# Freedom_Board_Interface.net
KiCad netlist of a schematic drawn in Altium Designer
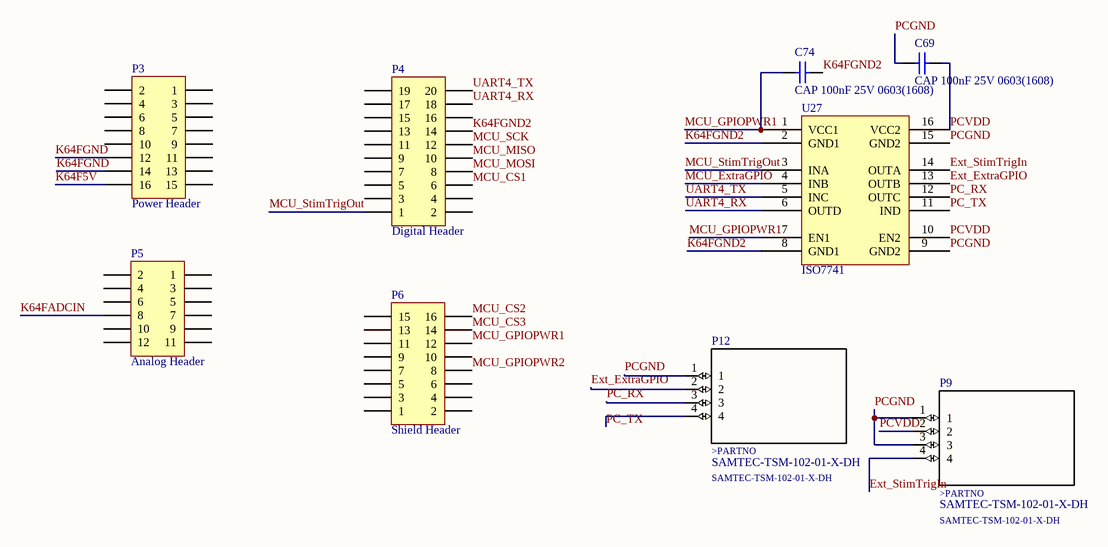
[diagram p0: Freedom Board Interface.SchDoc]

(export (version "E")
  (design (tool "Eeschema 10.0.6"))
  (components
    (comp (ref "C69")
      (value "CAP 100nF 25V 0603(1608)")
      (footprint "CAPC0603(1608)100_N")
      (description "CAP 100nF 25V ±20% 0603 (1608 Metric) Thickness 1mm SMD")
      (fields (field (name "TOLERANCE") "Â±20%"))
      (libsource (lib "Altium Content Vault") (part "CAP"))
    )
    (comp (ref "C74")
      (value "CAP 100nF 25V 0603(1608)")
      (footprint "CAPC0603(1608)100_N")
      (description "CAP 100nF 25V ±20% 0603 (1608 Metric) Thickness 1mm SMD")
      (fields (field (name "TOLERANCE") "Â±20%"))
      (libsource (lib "Altium Content Vault") (part "CAP"))
    )
    (comp (ref "P3")
      (value "Power Header")
      (footprint "HDR2X8")
      (description "Header, 8-Pin, Dual row")
      (fields (field (name "PUBLISHER") "Altium Limited"))
      (libsource (lib "") (part "Header 8X2_1"))
    )
    (comp (ref "P4")
      (value "Digital Header")
      (footprint "HDR2X10")
      (description "Header, 10-Pin, Dual row")
      (fields (field (name "PUBLISHER") "Altium Limited"))
      (libsource (lib "Miscellaneous Connectors") (part "Header 10X2"))
    )
    (comp (ref "P5")
      (value "Analog Header")
      (footprint "HDR2X6")
      (description "Header, 6-Pin, Dual row")
      (fields (field (name "PUBLISHER") "Altium Limited"))
      (libsource (lib "Miscellaneous Connectors") (part "Header 6X2"))
    )
    (comp (ref "P6")
      (value "Shield Header")
      (footprint "HDR2X8")
      (description "Header, 8-Pin, Dual row")
      (fields (field (name "PUBLISHER") "Altium Limited"))
      (libsource (lib "Miscellaneous Connectors") (part "Header 8X2"))
    )
    (comp (ref "P9")
      (value "SAMTEC-TSM-102-01-X-DH")
      (footprint "*SAMTEC-TSM-102-01-X-DH")
      (description "Conn Unshrouded Header HDR 4 POS 2.54mm Solder RA SMD")
      (fields (field (name "MF") "Samtec Inc.") (field (name "DIGI-KEY_PART_NUMBER") "TSM-102-01-F-DH-ND"))
      (libsource (lib "SAMTEC-TSM-102-01-X-DH") (part "SAMTEC-TSM-102-01-X-DH"))
    )
    (comp (ref "P12")
      (value "SAMTEC-TSM-102-01-X-DH")
      (footprint "*SAMTEC-TSM-102-01-X-DH")
      (description "Conn Unshrouded Header HDR 4 POS 2.54mm Solder RA SMD")
      (fields (field (name "MF") "Samtec Inc.") (field (name "DIGI-KEY_PART_NUMBER") "TSM-102-01-F-DH-ND"))
      (libsource (lib "SAMTEC-TSM-102-01-X-DH") (part "SAMTEC-TSM-102-01-X-DH"))
    )
    (comp (ref "U27")
      (value "ISO7741")
      (footprint "16SSOP JEDEC MO-137 AB")
      (libsource (lib "ar5113_Altium_Library") (part "ISO7741"))
    )
  )
  (nets
    (net (code "1") (name "/Ext_ExtraGPIO") (class "Default")
      (node (ref "P12") (pin "2") (pinfunction "2_2") (pintype "bidirectional"))
      (node (ref "U27") (pin "13") (pinfunction "OUTB_13") (pintype "passive"))
    )
    (net (code "2") (name "/Ext_StimTrigIn") (class "Default")
      (node (ref "P9") (pin "4") (pinfunction "4_4") (pintype "bidirectional"))
      (node (ref "U27") (pin "14") (pinfunction "OUTA_14") (pintype "passive"))
    )
    (net (code "3") (name "/K64F5V") (class "Default")
      (node (ref "P3") (pin "16") (pinfunction "16_16") (pintype "passive"))
    )
    (net (code "4") (name "/K64FADCIN") (class "Default")
      (node (ref "P5") (pin "8") (pinfunction "8_8") (pintype "passive"))
    )
    (net (code "5") (name "/K64FGND") (class "Default")
      (node (ref "P3") (pin "12") (pinfunction "12_12") (pintype "passive"))
      (node (ref "P3") (pin "14") (pinfunction "14_14") (pintype "passive"))
    )
    (net (code "6") (name "/K64FGND2") (class "Default")
      (node (ref "C74") (pin "1") (pinfunction "1_1") (pintype "passive"))
      (node (ref "P4") (pin "14") (pinfunction "14_14") (pintype "passive"))
      (node (ref "U27") (pin "2") (pinfunction "GND1_2") (pintype "passive"))
      (node (ref "U27") (pin "8") (pinfunction "GND1_8") (pintype "passive"))
    )
    (net (code "7") (name "/MCU_CS1") (class "Default")
      (node (ref "P4") (pin "6") (pinfunction "6_6") (pintype "passive"))
    )
    (net (code "8") (name "/MCU_CS2") (class "Default")
      (node (ref "P6") (pin "16") (pinfunction "16_16") (pintype "passive"))
    )
    (net (code "9") (name "/MCU_CS3") (class "Default")
      (node (ref "P6") (pin "14") (pinfunction "14_14") (pintype "passive"))
    )
    (net (code "10") (name "/MCU_ExtraGPIO") (class "Default")
      (node (ref "U27") (pin "4") (pinfunction "INB_4") (pintype "passive"))
    )
    (net (code "11") (name "/MCU_GPIOPWR1") (class "Default")
      (node (ref "C74") (pin "2") (pinfunction "2_2") (pintype "passive"))
      (node (ref "P6") (pin "12") (pinfunction "12_12") (pintype "passive"))
      (node (ref "U27") (pin "1") (pinfunction "VCC1_1") (pintype "passive"))
      (node (ref "U27") (pin "7") (pinfunction "EN1_7") (pintype "passive"))
    )
    (net (code "12") (name "/MCU_GPIOPWR2") (class "Default")
      (node (ref "P6") (pin "8") (pinfunction "8_8") (pintype "passive"))
    )
    (net (code "13") (name "/MCU_MISO") (class "Default")
      (node (ref "P4") (pin "10") (pinfunction "10_10") (pintype "passive"))
    )
    (net (code "14") (name "/MCU_MOSI") (class "Default")
      (node (ref "P4") (pin "8") (pinfunction "8_8") (pintype "passive"))
    )
    (net (code "15") (name "/MCU_SCK") (class "Default")
      (node (ref "P4") (pin "12") (pinfunction "12_12") (pintype "passive"))
    )
    (net (code "16") (name "/MCU_StimTrigOut") (class "Default")
      (node (ref "P4") (pin "1") (pinfunction "1_1") (pintype "passive"))
      (node (ref "U27") (pin "3") (pinfunction "INA_3") (pintype "passive"))
    )
    (net (code "17") (name "/PCGND") (class "Default")
      (node (ref "C69") (pin "2") (pinfunction "2_2") (pintype "passive"))
      (node (ref "P12") (pin "1") (pinfunction "1_1") (pintype "bidirectional"))
      (node (ref "P9") (pin "1") (pinfunction "1_1") (pintype "bidirectional"))
      (node (ref "P9") (pin "3") (pinfunction "3_3") (pintype "bidirectional"))
      (node (ref "U27") (pin "15") (pinfunction "GND2_15") (pintype "passive"))
      (node (ref "U27") (pin "9") (pinfunction "GND2_9") (pintype "passive"))
    )
    (net (code "18") (name "/PCVDD") (class "Default")
      (node (ref "C69") (pin "1") (pinfunction "1_1") (pintype "passive"))
      (node (ref "P9") (pin "2") (pinfunction "2_2") (pintype "bidirectional"))
      (node (ref "U27") (pin "10") (pinfunction "EN2_10") (pintype "passive"))
      (node (ref "U27") (pin "16") (pinfunction "VCC2_16") (pintype "passive"))
    )
    (net (code "19") (name "/PC_RX") (class "Default")
      (node (ref "P12") (pin "3") (pinfunction "3_3") (pintype "bidirectional"))
      (node (ref "U27") (pin "12") (pinfunction "OUTC_12") (pintype "passive"))
    )
    (net (code "20") (name "/PC_TX") (class "Default")
      (node (ref "P12") (pin "4") (pinfunction "4_4") (pintype "bidirectional"))
      (node (ref "U27") (pin "11") (pinfunction "IND_11") (pintype "passive"))
    )
    (net (code "21") (name "/UART4_RX") (class "Default")
      (node (ref "P4") (pin "18") (pinfunction "18_18") (pintype "passive"))
      (node (ref "U27") (pin "6") (pinfunction "OUTD_6") (pintype "passive"))
    )
    (net (code "22") (name "/UART4_TX") (class "Default")
      (node (ref "P4") (pin "20") (pinfunction "20_20") (pintype "passive"))
      (node (ref "U27") (pin "5") (pinfunction "INC_5") (pintype "passive"))
    )
    (net (code "23") (name "unconnected-(P3-Pad1)") (class "Default")
      (node (ref "P3") (pin "1") (pinfunction "1_1") (pintype "passive"))
    )
    (net (code "24") (name "unconnected-(P3-Pad2)") (class "Default")
      (node (ref "P3") (pin "2") (pinfunction "2_2") (pintype "passive"))
    )
    (net (code "25") (name "unconnected-(P3-Pad3)") (class "Default")
      (node (ref "P3") (pin "3") (pinfunction "3_3") (pintype "passive"))
    )
    (net (code "26") (name "unconnected-(P3-Pad4)") (class "Default")
      (node (ref "P3") (pin "4") (pinfunction "4_4") (pintype "passive"))
    )
    (net (code "27") (name "unconnected-(P3-Pad5)") (class "Default")
      (node (ref "P3") (pin "5") (pinfunction "5_5") (pintype "passive"))
    )
    (net (code "28") (name "unconnected-(P3-Pad6)") (class "Default")
      (node (ref "P3") (pin "6") (pinfunction "6_6") (pintype "passive"))
    )
    (net (code "29") (name "unconnected-(P3-Pad7)") (class "Default")
      (node (ref "P3") (pin "7") (pinfunction "7_7") (pintype "passive"))
    )
    (net (code "30") (name "unconnected-(P3-Pad8)") (class "Default")
      (node (ref "P3") (pin "8") (pinfunction "8_8") (pintype "passive"))
    )
    (net (code "31") (name "unconnected-(P3-Pad9)") (class "Default")
      (node (ref "P3") (pin "9") (pinfunction "9_9") (pintype "passive"))
    )
    (net (code "32") (name "unconnected-(P3-Pad10)") (class "Default")
      (node (ref "P3") (pin "10") (pinfunction "10_10") (pintype "passive"))
    )
    (net (code "33") (name "unconnected-(P3-Pad11)") (class "Default")
      (node (ref "P3") (pin "11") (pinfunction "11_11") (pintype "passive"))
    )
    (net (code "34") (name "unconnected-(P3-Pad13)") (class "Default")
      (node (ref "P3") (pin "13") (pinfunction "13_13") (pintype "passive"))
    )
    (net (code "35") (name "unconnected-(P3-Pad15)") (class "Default")
      (node (ref "P3") (pin "15") (pinfunction "15_15") (pintype "passive"))
    )
    (net (code "36") (name "unconnected-(P4-Pad2)") (class "Default")
      (node (ref "P4") (pin "2") (pinfunction "2_2") (pintype "passive"))
    )
    (net (code "37") (name "unconnected-(P4-Pad3)") (class "Default")
      (node (ref "P4") (pin "3") (pinfunction "3_3") (pintype "passive"))
    )
    (net (code "38") (name "unconnected-(P4-Pad4)") (class "Default")
      (node (ref "P4") (pin "4") (pinfunction "4_4") (pintype "passive"))
    )
    (net (code "39") (name "unconnected-(P4-Pad5)") (class "Default")
      (node (ref "P4") (pin "5") (pinfunction "5_5") (pintype "passive"))
    )
    (net (code "40") (name "unconnected-(P4-Pad7)") (class "Default")
      (node (ref "P4") (pin "7") (pinfunction "7_7") (pintype "passive"))
    )
    (net (code "41") (name "unconnected-(P4-Pad9)") (class "Default")
      (node (ref "P4") (pin "9") (pinfunction "9_9") (pintype "passive"))
    )
    (net (code "42") (name "unconnected-(P4-Pad11)") (class "Default")
      (node (ref "P4") (pin "11") (pinfunction "11_11") (pintype "passive"))
    )
    (net (code "43") (name "unconnected-(P4-Pad13)") (class "Default")
      (node (ref "P4") (pin "13") (pinfunction "13_13") (pintype "passive"))
    )
    (net (code "44") (name "unconnected-(P4-Pad15)") (class "Default")
      (node (ref "P4") (pin "15") (pinfunction "15_15") (pintype "passive"))
    )
    (net (code "45") (name "unconnected-(P4-Pad16)") (class "Default")
      (node (ref "P4") (pin "16") (pinfunction "16_16") (pintype "passive"))
    )
    (net (code "46") (name "unconnected-(P4-Pad17)") (class "Default")
      (node (ref "P4") (pin "17") (pinfunction "17_17") (pintype "passive"))
    )
    (net (code "47") (name "unconnected-(P4-Pad19)") (class "Default")
      (node (ref "P4") (pin "19") (pinfunction "19_19") (pintype "passive"))
    )
    (net (code "48") (name "unconnected-(P5-Pad1)") (class "Default")
      (node (ref "P5") (pin "1") (pinfunction "1_1") (pintype "passive"))
    )
    (net (code "49") (name "unconnected-(P5-Pad2)") (class "Default")
      (node (ref "P5") (pin "2") (pinfunction "2_2") (pintype "passive"))
    )
    (net (code "50") (name "unconnected-(P5-Pad3)") (class "Default")
      (node (ref "P5") (pin "3") (pinfunction "3_3") (pintype "passive"))
    )
    (net (code "51") (name "unconnected-(P5-Pad4)") (class "Default")
      (node (ref "P5") (pin "4") (pinfunction "4_4") (pintype "passive"))
    )
    (net (code "52") (name "unconnected-(P5-Pad5)") (class "Default")
      (node (ref "P5") (pin "5") (pinfunction "5_5") (pintype "passive"))
    )
    (net (code "53") (name "unconnected-(P5-Pad6)") (class "Default")
      (node (ref "P5") (pin "6") (pinfunction "6_6") (pintype "passive"))
    )
    (net (code "54") (name "unconnected-(P5-Pad7)") (class "Default")
      (node (ref "P5") (pin "7") (pinfunction "7_7") (pintype "passive"))
    )
    (net (code "55") (name "unconnected-(P5-Pad9)") (class "Default")
      (node (ref "P5") (pin "9") (pinfunction "9_9") (pintype "passive"))
    )
    (net (code "56") (name "unconnected-(P5-Pad10)") (class "Default")
      (node (ref "P5") (pin "10") (pinfunction "10_10") (pintype "passive"))
    )
    (net (code "57") (name "unconnected-(P5-Pad11)") (class "Default")
      (node (ref "P5") (pin "11") (pinfunction "11_11") (pintype "passive"))
    )
    (net (code "58") (name "unconnected-(P5-Pad12)") (class "Default")
      (node (ref "P5") (pin "12") (pinfunction "12_12") (pintype "passive"))
    )
    (net (code "59") (name "unconnected-(P6-Pad1)") (class "Default")
      (node (ref "P6") (pin "1") (pinfunction "1_1") (pintype "passive"))
    )
    (net (code "60") (name "unconnected-(P6-Pad2)") (class "Default")
      (node (ref "P6") (pin "2") (pinfunction "2_2") (pintype "passive"))
    )
    (net (code "61") (name "unconnected-(P6-Pad3)") (class "Default")
      (node (ref "P6") (pin "3") (pinfunction "3_3") (pintype "passive"))
    )
    (net (code "62") (name "unconnected-(P6-Pad4)") (class "Default")
      (node (ref "P6") (pin "4") (pinfunction "4_4") (pintype "passive"))
    )
    (net (code "63") (name "unconnected-(P6-Pad5)") (class "Default")
      (node (ref "P6") (pin "5") (pinfunction "5_5") (pintype "passive"))
    )
    (net (code "64") (name "unconnected-(P6-Pad6)") (class "Default")
      (node (ref "P6") (pin "6") (pinfunction "6_6") (pintype "passive"))
    )
    (net (code "65") (name "unconnected-(P6-Pad7)") (class "Default")
      (node (ref "P6") (pin "7") (pinfunction "7_7") (pintype "passive"))
    )
    (net (code "66") (name "unconnected-(P6-Pad9)") (class "Default")
      (node (ref "P6") (pin "9") (pinfunction "9_9") (pintype "passive"))
    )
    (net (code "67") (name "unconnected-(P6-Pad10)") (class "Default")
      (node (ref "P6") (pin "10") (pinfunction "10_10") (pintype "passive"))
    )
    (net (code "68") (name "unconnected-(P6-Pad11)") (class "Default")
      (node (ref "P6") (pin "11") (pinfunction "11_11") (pintype "passive"))
    )
    (net (code "69") (name "unconnected-(P6-Pad13)") (class "Default")
      (node (ref "P6") (pin "13") (pinfunction "13_13") (pintype "passive"))
    )
    (net (code "70") (name "unconnected-(P6-Pad15)") (class "Default")
      (node (ref "P6") (pin "15") (pinfunction "15_15") (pintype "passive"))
    )
  )
)
